# contactor-feedback-divider.net
KiCad netlist of a schematic drawn in Altium Designer
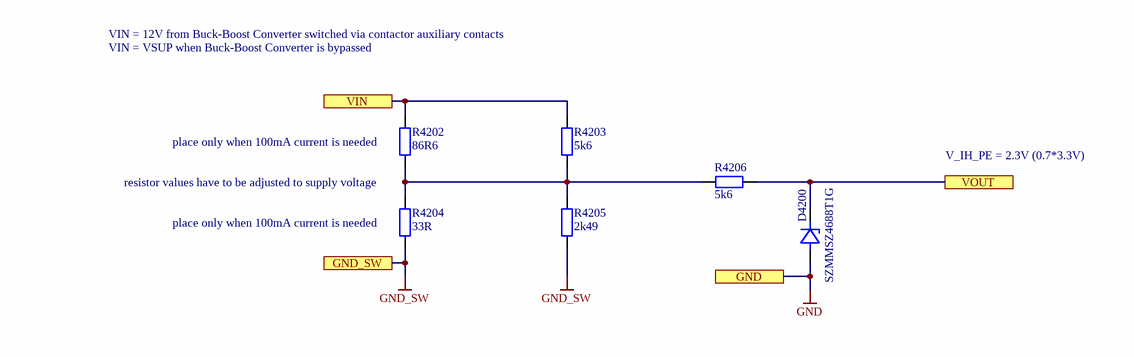
[diagram p0: contactor-feedback-divider.SchDoc]

(export (version "E")
  (design (tool "Eeschema 10.0.6"))
  (components
    (comp (ref "D4200")
      (value "SZMMSZ4688T1G")
      (footprint "SOD-123_CASE-425-04-ISSUE-G")
      (description "Zener Diode")
      (fields (field (name "MANUFACTURER") "ON Semiconductor"))
      (libsource (lib "OE750") (part "D_Zener"))
    )
    (comp (ref "R4202")
      (value "86R6")
      (footprint "RESC5025X07N")
      (description "SMD Resistor 86R6 2010")
      (fields (field (name "PART NUMBER") "gen_R_86R6_2010") (field (name "TOLERANCE") "1%"))
      (libsource (lib "OE750") (part "R"))
    )
    (comp (ref "R4203")
      (value "5k6")
      (footprint "RESC1005X04N")
      (description "SMD Resistor 5k6 0402")
      (fields (field (name "PART NUMBER") "gen_R_5k6_0402") (field (name "TOLERANCE") "1%"))
      (libsource (lib "OE750") (part "R"))
    )
    (comp (ref "R4204")
      (value "33R")
      (footprint "RESC5025X07N")
      (description "SMD Resistor 33R 2010")
      (fields (field (name "PART NUMBER") "gen_R_33R_2010") (field (name "TOLERANCE") "1%"))
      (libsource (lib "OE750") (part "R"))
    )
    (comp (ref "R4205")
      (value "2k49")
      (footprint "RESC1005X04N")
      (description "SMD Resistor 2k49 0402")
      (fields (field (name "PART NUMBER") "gen_R_2k49_0402") (field (name "TOLERANCE") "1%"))
      (libsource (lib "OE750") (part "R"))
    )
    (comp (ref "R4206")
      (value "5k6")
      (footprint "RESC1005X04N")
      (description "SMD Resistor 5k6 0402")
      (fields (field (name "PART NUMBER") "gen_R_5k6_0402") (field (name "TOLERANCE") "1%"))
      (libsource (lib "OE750") (part "R"))
    )
  )
  (nets
    (net (code "1") (name "/VIN") (class "Default")
      (node (ref "R4202") (pin "2") (pinfunction "2_2") (pintype "passive"))
      (node (ref "R4203") (pin "2") (pinfunction "2_2") (pintype "passive"))
    )
    (net (code "2") (name "/VOUT") (class "Default")
      (node (ref "D4200") (pin "1") (pinfunction "K_1") (pintype "passive"))
      (node (ref "R4206") (pin "1") (pinfunction "1_1") (pintype "passive"))
    )
    (net (code "3") (name "GND") (class "Default")
      (node (ref "D4200") (pin "2") (pinfunction "A_2") (pintype "passive"))
    )
    (net (code "4") (name "GND_SW") (class "Default")
      (node (ref "R4204") (pin "1") (pinfunction "1_1") (pintype "passive"))
      (node (ref "R4205") (pin "1") (pinfunction "1_1") (pintype "passive"))
    )
    (net (code "5") (name "Net-(R4202-Pad1)") (class "Default")
      (node (ref "R4202") (pin "1") (pinfunction "1_1") (pintype "passive"))
      (node (ref "R4203") (pin "1") (pinfunction "1_1") (pintype "passive"))
      (node (ref "R4204") (pin "2") (pinfunction "2_2") (pintype "passive"))
      (node (ref "R4205") (pin "2") (pinfunction "2_2") (pintype "passive"))
      (node (ref "R4206") (pin "2") (pinfunction "2_2") (pintype "passive"))
    )
  )
)
